# H_lice31-LED_1.net
KiCad netlist of a schematic drawn in Altium Designer
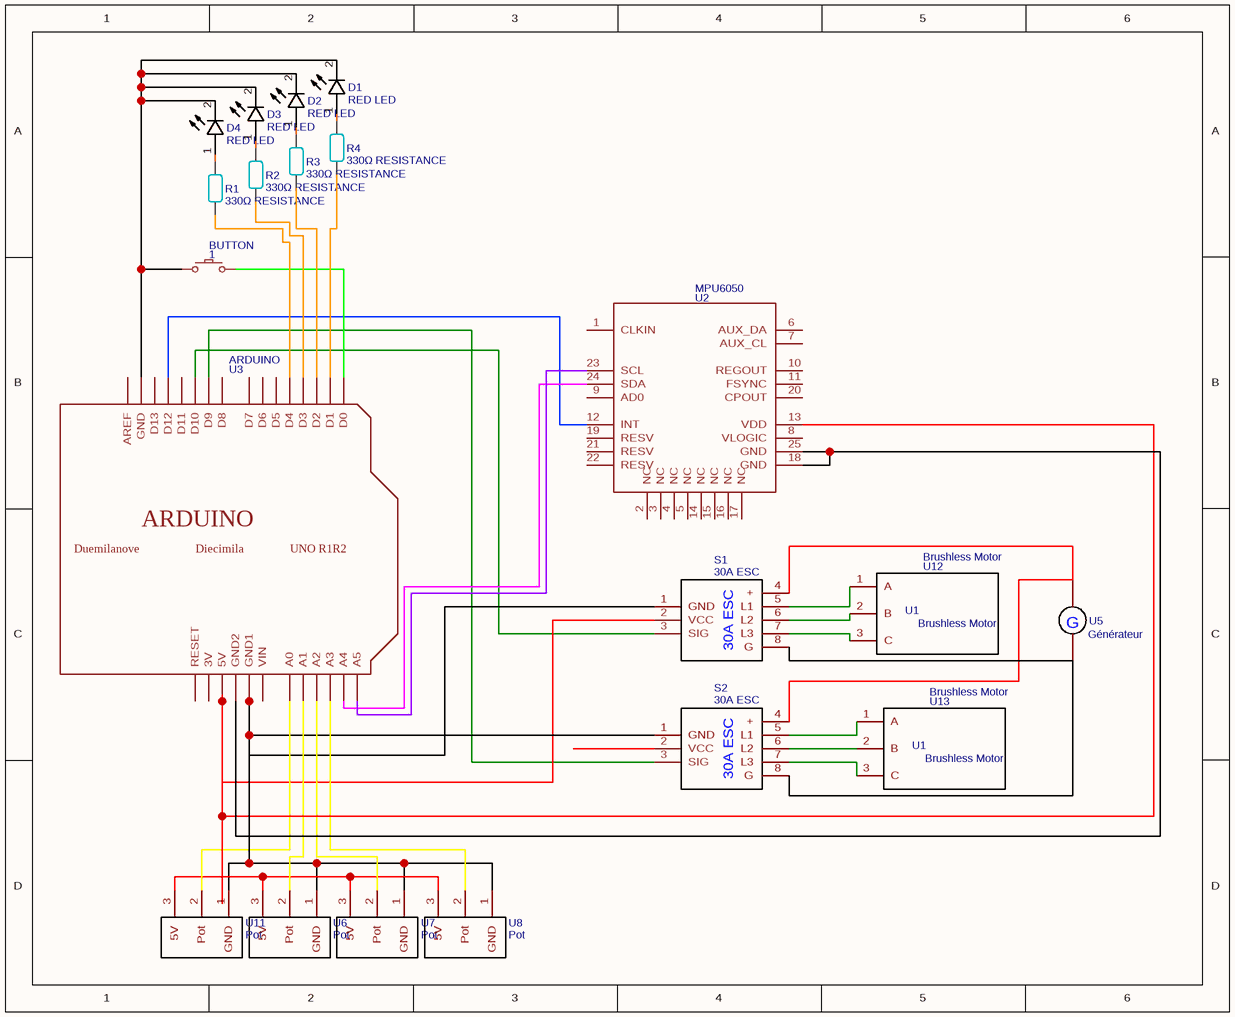
[diagram p0: Hélice31-LED (1).schdoc]

(export (version "E")
  (design (tool "Eeschema 10.0.6"))
  (components
    (comp (ref "1")
      (value "BUTTON")
      (fields (field (name "CONTRIBUTOR") "LorenzoVonMatterhorn"))
      (libsource (lib "altium-import") (part "root_0_BUTTON_"))
    )
    (comp (ref "D1")
      (value "RED LED")
      (fields
        (field (name "MANUFACTURER") "VccLite")
        (field (name "MANUFACTURER PART") "5600")
        (field (name "CONTRIBUTOR") "peycar")
      )
      (libsource (lib "altium-import") (part "root_3_RED LED_"))
    )
    (comp (ref "D2")
      (value "RED LED")
      (fields
        (field (name "MANUFACTURER") "VccLite")
        (field (name "MANUFACTURER PART") "5600")
        (field (name "CONTRIBUTOR") "peycar")
      )
      (libsource (lib "altium-import") (part "root_3_RED LED_"))
    )
    (comp (ref "D3")
      (value "RED LED")
      (fields
        (field (name "MANUFACTURER") "VccLite")
        (field (name "MANUFACTURER PART") "5600")
        (field (name "CONTRIBUTOR") "peycar")
      )
      (libsource (lib "altium-import") (part "root_3_RED LED_"))
    )
    (comp (ref "D4")
      (value "RED LED")
      (fields
        (field (name "MANUFACTURER") "VccLite")
        (field (name "MANUFACTURER PART") "5600")
        (field (name "CONTRIBUTOR") "peycar")
      )
      (libsource (lib "altium-import") (part "root_3_RED LED_"))
    )
    (comp (ref "R1")
      (value "330Ω RESISTANCE")
      (fields (field (name "CONTRIBUTOR") "pritams07"))
      (libsource (lib "altium-import") (part "root_1_330Ω RESISTANCE_"))
    )
    (comp (ref "R2")
      (value "330Ω RESISTANCE")
      (fields (field (name "CONTRIBUTOR") "pritams07"))
      (libsource (lib "altium-import") (part "root_1_330Ω RESISTANCE_"))
    )
    (comp (ref "R3")
      (value "330Ω RESISTANCE")
      (fields (field (name "CONTRIBUTOR") "pritams07"))
      (libsource (lib "altium-import") (part "root_1_330Ω RESISTANCE_"))
    )
    (comp (ref "R4")
      (value "330Ω RESISTANCE")
      (fields (field (name "CONTRIBUTOR") "pritams07"))
      (libsource (lib "altium-import") (part "root_1_330Ω RESISTANCE_"))
    )
    (comp (ref "S1")
      (value "30A ESC")
      (fields (field (name "CONTRIBUTOR") "ilos"))
      (libsource (lib "altium-import") (part "root_3_30A ESC_"))
    )
    (comp (ref "S2")
      (value "30A ESC")
      (fields (field (name "CONTRIBUTOR") "ilos"))
      (libsource (lib "altium-import") (part "root_3_30A ESC_"))
    )
    (comp (ref "U2") (value "MPU6050") (libsource (lib "altium-import") (part "root_0_MPU6050_")))
    (comp (ref "U3")
      (value "ARDUINO")
      (fields (field (name "CONTRIBUTOR") "Adafruit"))
      (libsource (lib "altium-import") (part "root_0_ARDUINO_"))
    )
    (comp (ref "U5")
      (value "Générateur")
      (fields (field (name "CONTRIBUTOR") "oswin03"))
      (libsource (lib "altium-import") (part "root_2_Générateur_"))
    )
    (comp (ref "U6")
      (value "Pot")
      (fields (field (name "CONTRIBUTOR") "merlu.timothee"))
      (libsource (lib "altium-import") (part "root_1_Pot_"))
    )
    (comp (ref "U7")
      (value "Pot")
      (fields (field (name "CONTRIBUTOR") "merlu.timothee"))
      (libsource (lib "altium-import") (part "root_1_Pot_"))
    )
    (comp (ref "U8")
      (value "Pot")
      (fields (field (name "CONTRIBUTOR") "merlu.timothee"))
      (libsource (lib "altium-import") (part "root_1_Pot_"))
    )
    (comp (ref "U11")
      (value "Pot")
      (fields (field (name "CONTRIBUTOR") "merlu.timothee"))
      (libsource (lib "altium-import") (part "root_1_Pot_"))
    )
    (comp (ref "U12")
      (value "Brushless Motor")
      (fields (field (name "CONTRIBUTOR") "Droners"))
      (libsource (lib "altium-import") (part "root_0_Brushless Motor_"))
    )
    (comp (ref "U13")
      (value "Brushless Motor")
      (fields (field (name "CONTRIBUTOR") "Droners"))
      (libsource (lib "altium-import") (part "root_0_Brushless Motor_"))
    )
  )
  (nets
    (net (code "1") (name "Net-(1-PadP$ACTIVE)") (class "Default")
      (node (ref "1") (pin "P$ACTIVE") (pinfunction "P$ACTIVE_P$ACTIVE") (pintype "passive"))
      (node (ref "U3") (pin "D0") (pinfunction "D0_D0") (pintype "passive"))
    )
    (net (code "2") (name "Net-(D1-A)") (class "Default")
      (node (ref "D1") (pin "1") (pinfunction "A_1") (pintype "passive"))
      (node (ref "R4") (pin "2") (pinfunction "2_2") (pintype "passive"))
    )
    (net (code "3") (name "Net-(D1-K)") (class "Default")
      (node (ref "1") (pin "P$GND") (pinfunction "P$GND_P$GND") (pintype "passive"))
      (node (ref "D1") (pin "2") (pinfunction "K_2") (pintype "passive"))
      (node (ref "D2") (pin "2") (pinfunction "K_2") (pintype "passive"))
      (node (ref "D3") (pin "2") (pinfunction "K_2") (pintype "passive"))
      (node (ref "D4") (pin "2") (pinfunction "K_2") (pintype "passive"))
      (node (ref "U3") (pin "GND") (pinfunction "GND_GND") (pintype "passive"))
    )
    (net (code "4") (name "Net-(D2-A)") (class "Default")
      (node (ref "D2") (pin "1") (pinfunction "A_1") (pintype "passive"))
      (node (ref "R3") (pin "2") (pinfunction "2_2") (pintype "passive"))
    )
    (net (code "5") (name "Net-(D3-A)") (class "Default")
      (node (ref "D3") (pin "1") (pinfunction "A_1") (pintype "passive"))
      (node (ref "R2") (pin "2") (pinfunction "2_2") (pintype "passive"))
    )
    (net (code "6") (name "Net-(D4-A)") (class "Default")
      (node (ref "D4") (pin "1") (pinfunction "A_1") (pintype "passive"))
      (node (ref "R1") (pin "2") (pinfunction "2_2") (pintype "passive"))
    )
    (net (code "7") (name "Net-(R1-Pad1)") (class "Default")
      (node (ref "R1") (pin "1") (pinfunction "1_1") (pintype "passive"))
      (node (ref "U3") (pin "D4") (pinfunction "D4_D4") (pintype "passive"))
    )
    (net (code "8") (name "Net-(R2-Pad1)") (class "Default")
      (node (ref "R2") (pin "1") (pinfunction "1_1") (pintype "passive"))
      (node (ref "U3") (pin "D3") (pinfunction "D3_D3") (pintype "passive"))
    )
    (net (code "9") (name "Net-(R3-Pad1)") (class "Default")
      (node (ref "R3") (pin "1") (pinfunction "1_1") (pintype "passive"))
      (node (ref "U3") (pin "D2") (pinfunction "D2_D2") (pintype "passive"))
    )
    (net (code "10") (name "Net-(R4-Pad1)") (class "Default")
      (node (ref "R4") (pin "1") (pinfunction "1_1") (pintype "passive"))
      (node (ref "U3") (pin "D1") (pinfunction "D1_D1") (pintype "passive"))
    )
    (net (code "11") (name "Net-(S1-+)") (class "Default")
      (node (ref "S1") (pin "4") (pinfunction "+_4") (pintype "passive"))
      (node (ref "S2") (pin "4") (pinfunction "+_4") (pintype "passive"))
    )
    (net (code "12") (name "Net-(S1-G)") (class "Default")
      (node (ref "S1") (pin "8") (pinfunction "G_8") (pintype "passive"))
      (node (ref "S2") (pin "8") (pinfunction "G_8") (pintype "passive"))
    )
    (net (code "13") (name "Net-(S1-GND)") (class "Default")
      (node (ref "S1") (pin "1") (pinfunction "GND_1") (pintype "passive"))
      (node (ref "S2") (pin "1") (pinfunction "GND_1") (pintype "passive"))
      (node (ref "U11") (pin "1") (pinfunction "GND_1") (pintype "passive"))
      (node (ref "U3") (pin "GND1") (pinfunction "GND1_GND1") (pintype "passive"))
      (node (ref "U6") (pin "1") (pinfunction "GND_1") (pintype "passive"))
      (node (ref "U7") (pin "1") (pinfunction "GND_1") (pintype "passive"))
      (node (ref "U8") (pin "1") (pinfunction "GND_1") (pintype "passive"))
    )
    (net (code "14") (name "Net-(S1-L1)") (class "Default")
      (node (ref "S1") (pin "5") (pinfunction "L1_5") (pintype "passive"))
      (node (ref "U12") (pin "1") (pinfunction "A_1") (pintype "passive"))
    )
    (net (code "15") (name "Net-(S1-L2)") (class "Default")
      (node (ref "S1") (pin "6") (pinfunction "L2_6") (pintype "passive"))
      (node (ref "U12") (pin "2") (pinfunction "B_2") (pintype "passive"))
    )
    (net (code "16") (name "Net-(S1-L3)") (class "Default")
      (node (ref "S1") (pin "7") (pinfunction "L3_7") (pintype "passive"))
      (node (ref "U12") (pin "3") (pinfunction "C_3") (pintype "passive"))
    )
    (net (code "17") (name "Net-(S1-SIG)") (class "Default")
      (node (ref "S1") (pin "3") (pinfunction "SIG_3") (pintype "passive"))
      (node (ref "U3") (pin "D10") (pinfunction "D10_D10") (pintype "passive"))
    )
    (net (code "18") (name "Net-(S1-VCC)") (class "Default")
      (node (ref "S1") (pin "2") (pinfunction "VCC_2") (pintype "passive"))
      (node (ref "U2") (pin "13") (pinfunction "VDD_13") (pintype "passive"))
      (node (ref "U3") (pin "5V") (pinfunction "5V_5V") (pintype "passive"))
    )
    (net (code "19") (name "Net-(S2-L1)") (class "Default")
      (node (ref "S2") (pin "5") (pinfunction "L1_5") (pintype "passive"))
      (node (ref "U13") (pin "1") (pinfunction "A_1") (pintype "passive"))
    )
    (net (code "20") (name "Net-(S2-L2)") (class "Default")
      (node (ref "S2") (pin "6") (pinfunction "L2_6") (pintype "passive"))
      (node (ref "U13") (pin "2") (pinfunction "B_2") (pintype "passive"))
    )
    (net (code "21") (name "Net-(S2-L3)") (class "Default")
      (node (ref "S2") (pin "7") (pinfunction "L3_7") (pintype "passive"))
      (node (ref "U13") (pin "3") (pinfunction "C_3") (pintype "passive"))
    )
    (net (code "22") (name "Net-(S2-SIG)") (class "Default")
      (node (ref "S2") (pin "3") (pinfunction "SIG_3") (pintype "passive"))
      (node (ref "U3") (pin "D9") (pinfunction "D9_D9") (pintype "passive"))
    )
    (net (code "23") (name "Net-(U2-GND-Pad18)") (class "Default")
      (node (ref "U2") (pin "18") (pinfunction "GND_18") (pintype "passive"))
      (node (ref "U2") (pin "25") (pinfunction "GND_25") (pintype "passive"))
      (node (ref "U3") (pin "GND2") (pinfunction "GND2_GND2") (pintype "passive"))
    )
    (net (code "24") (name "Net-(U2-INT)") (class "Default")
      (node (ref "U2") (pin "12") (pinfunction "INT_12") (pintype "passive"))
      (node (ref "U3") (pin "D12") (pinfunction "D12_D12") (pintype "passive"))
    )
    (net (code "25") (name "Net-(U2-SCL)") (class "Default")
      (node (ref "U2") (pin "23") (pinfunction "SCL_23") (pintype "passive"))
      (node (ref "U3") (pin "A5") (pinfunction "A5_A5") (pintype "passive"))
    )
    (net (code "26") (name "Net-(U2-SDA)") (class "Default")
      (node (ref "U2") (pin "24") (pinfunction "SDA_24") (pintype "passive"))
      (node (ref "U3") (pin "A4") (pinfunction "A4_A4") (pintype "passive"))
    )
    (net (code "27") (name "Net-(U6-Pot)") (class "Default")
      (node (ref "U3") (pin "A1") (pinfunction "A1_A1") (pintype "passive"))
      (node (ref "U6") (pin "2") (pinfunction "Pot_2") (pintype "passive"))
    )
    (net (code "28") (name "Net-(U7-Pot)") (class "Default")
      (node (ref "U3") (pin "A2") (pinfunction "A2_A2") (pintype "passive"))
      (node (ref "U7") (pin "2") (pinfunction "Pot_2") (pintype "passive"))
    )
    (net (code "29") (name "Net-(U8-Pot)") (class "Default")
      (node (ref "U3") (pin "A3") (pinfunction "A3_A3") (pintype "passive"))
      (node (ref "U8") (pin "2") (pinfunction "Pot_2") (pintype "passive"))
    )
    (net (code "30") (name "Net-(U11-5V)") (class "Default")
      (node (ref "U11") (pin "3") (pinfunction "5V_3") (pintype "passive"))
      (node (ref "U6") (pin "3") (pinfunction "5V_3") (pintype "passive"))
      (node (ref "U7") (pin "3") (pinfunction "5V_3") (pintype "passive"))
      (node (ref "U8") (pin "3") (pinfunction "5V_3") (pintype "passive"))
    )
    (net (code "31") (name "Net-(U11-Pot)") (class "Default")
      (node (ref "U11") (pin "2") (pinfunction "Pot_2") (pintype "passive"))
      (node (ref "U3") (pin "A0") (pinfunction "A0_A0") (pintype "passive"))
    )
    (net (code "32") (name "unconnected-(S2-VCC-Pad2)") (class "Default")
      (node (ref "S2") (pin "2") (pinfunction "VCC_2") (pintype "passive"))
    )
    (net (code "33") (name "unconnected-(U2-AD0-Pad9)") (class "Default")
      (node (ref "U2") (pin "9") (pinfunction "AD0_9") (pintype "passive"))
    )
    (net (code "34") (name "unconnected-(U2-AUX_CL-Pad7)") (class "Default")
      (node (ref "U2") (pin "7") (pinfunction "AUX_CL_7") (pintype "passive"))
    )
    (net (code "35") (name "unconnected-(U2-AUX_DA-Pad6)") (class "Default")
      (node (ref "U2") (pin "6") (pinfunction "AUX_DA_6") (pintype "passive"))
    )
    (net (code "36") (name "unconnected-(U2-CLKIN-Pad1)") (class "Default")
      (node (ref "U2") (pin "1") (pinfunction "CLKIN_1") (pintype "passive"))
    )
    (net (code "37") (name "unconnected-(U2-CPOUT-Pad20)") (class "Default")
      (node (ref "U2") (pin "20") (pinfunction "CPOUT_20") (pintype "passive"))
    )
    (net (code "38") (name "unconnected-(U2-FSYNC-Pad11)") (class "Default")
      (node (ref "U2") (pin "11") (pinfunction "FSYNC_11") (pintype "passive"))
    )
    (net (code "39") (name "unconnected-(U2-NC-Pad2)") (class "Default")
      (node (ref "U2") (pin "2") (pinfunction "NC_2") (pintype "passive"))
    )
    (net (code "40") (name "unconnected-(U2-NC-Pad3)") (class "Default")
      (node (ref "U2") (pin "3") (pinfunction "NC_3") (pintype "passive"))
    )
    (net (code "41") (name "unconnected-(U2-NC-Pad4)") (class "Default")
      (node (ref "U2") (pin "4") (pinfunction "NC_4") (pintype "passive"))
    )
    (net (code "42") (name "unconnected-(U2-NC-Pad5)") (class "Default")
      (node (ref "U2") (pin "5") (pinfunction "NC_5") (pintype "passive"))
    )
    (net (code "43") (name "unconnected-(U2-NC-Pad14)") (class "Default")
      (node (ref "U2") (pin "14") (pinfunction "NC_14") (pintype "passive"))
    )
    (net (code "44") (name "unconnected-(U2-NC-Pad15)") (class "Default")
      (node (ref "U2") (pin "15") (pinfunction "NC_15") (pintype "passive"))
    )
    (net (code "45") (name "unconnected-(U2-NC-Pad16)") (class "Default")
      (node (ref "U2") (pin "16") (pinfunction "NC_16") (pintype "passive"))
    )
    (net (code "46") (name "unconnected-(U2-NC-Pad17)") (class "Default")
      (node (ref "U2") (pin "17") (pinfunction "NC_17") (pintype "passive"))
    )
    (net (code "47") (name "unconnected-(U2-REGOUT-Pad10)") (class "Default")
      (node (ref "U2") (pin "10") (pinfunction "REGOUT_10") (pintype "passive"))
    )
    (net (code "48") (name "unconnected-(U2-RESV-Pad19)") (class "Default")
      (node (ref "U2") (pin "19") (pinfunction "RESV_19") (pintype "passive"))
    )
    (net (code "49") (name "unconnected-(U2-RESV-Pad21)") (class "Default")
      (node (ref "U2") (pin "21") (pinfunction "RESV_21") (pintype "passive"))
    )
    (net (code "50") (name "unconnected-(U2-RESV-Pad22)") (class "Default")
      (node (ref "U2") (pin "22") (pinfunction "RESV_22") (pintype "passive"))
    )
    (net (code "51") (name "unconnected-(U2-VLOGIC-Pad8)") (class "Default")
      (node (ref "U2") (pin "8") (pinfunction "VLOGIC_8") (pintype "passive"))
    )
    (net (code "52") (name "unconnected-(U3-Pad3V)") (class "Default")
      (node (ref "U3") (pin "3V") (pinfunction "3V_3V") (pintype "passive"))
    )
    (net (code "53") (name "unconnected-(U3-PadAREF)") (class "Default")
      (node (ref "U3") (pin "AREF") (pinfunction "AREF_AREF") (pintype "passive"))
    )
    (net (code "54") (name "unconnected-(U3-PadD5)") (class "Default")
      (node (ref "U3") (pin "D5") (pinfunction "D5_D5") (pintype "passive"))
    )
    (net (code "55") (name "unconnected-(U3-PadD6)") (class "Default")
      (node (ref "U3") (pin "D6") (pinfunction "D6_D6") (pintype "passive"))
    )
    (net (code "56") (name "unconnected-(U3-PadD7)") (class "Default")
      (node (ref "U3") (pin "D7") (pinfunction "D7_D7") (pintype "passive"))
    )
    (net (code "57") (name "unconnected-(U3-PadD8)") (class "Default")
      (node (ref "U3") (pin "D8") (pinfunction "D8_D8") (pintype "passive"))
    )
    (net (code "58") (name "unconnected-(U3-PadD11)") (class "Default")
      (node (ref "U3") (pin "D11") (pinfunction "D11_D11") (pintype "passive"))
    )
    (net (code "59") (name "unconnected-(U3-PadD13)") (class "Default")
      (node (ref "U3") (pin "D13") (pinfunction "D13_D13") (pintype "passive"))
    )
    (net (code "60") (name "unconnected-(U3-PadRESET)") (class "Default")
      (node (ref "U3") (pin "RESET") (pinfunction "RESET_RESET") (pintype "passive"))
    )
    (net (code "61") (name "unconnected-(U3-PadVIN)") (class "Default")
      (node (ref "U3") (pin "VIN") (pinfunction "VIN_VIN") (pintype "passive"))
    )
    (net (code "62") (name "unconnected-(U5-Pad1)") (class "Default")
      (node (ref "U5") (pin "1") (pinfunction "1_1") (pintype "passive"))
    )
    (net (code "63") (name "unconnected-(U5-Pad2)") (class "Default")
      (node (ref "U5") (pin "2") (pinfunction "2_2") (pintype "passive"))
    )
  )
)
